# Adafruit_CharlieWing.net
KiCad netlist of a schematic drawn in EAGLE
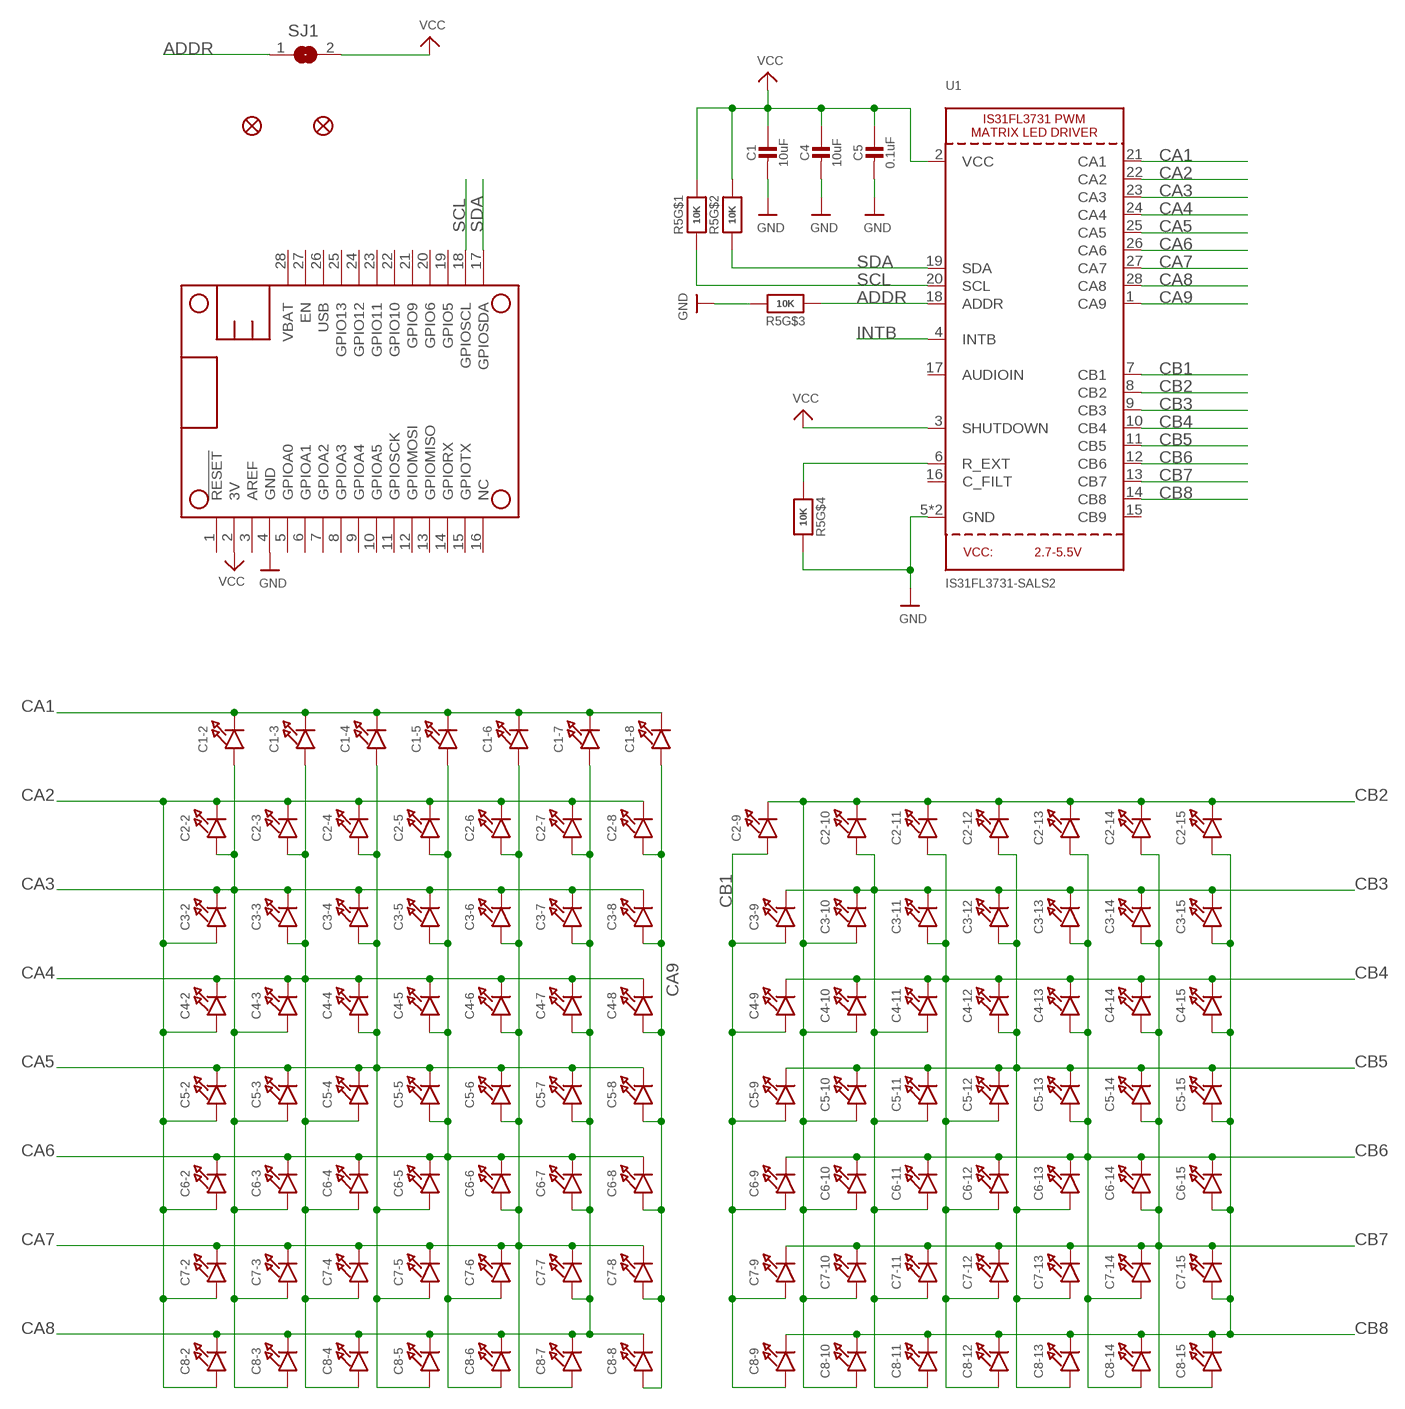
[diagram p0: schematic, sheet 1]

(export (version "E")
  (design (tool "Eeschema 10.0.6"))
  (components
    (comp (ref "C1")
      (value "10uF")
      (footprint "eagle-import:0805-NO")
      (libsource (lib "eagle-import") (part "CAP_CERAMIC0805-NOOUTLINE"))
    )
    (comp (ref "C1-2")
      (value "LED0603_NOOUTLINE")
      (footprint "eagle-import:CHIPLED_0603_NOOUTLINE")
      (libsource (lib "eagle-import") (part "LED0603_NOOUTLINE"))
    )
    (comp (ref "C1-3")
      (value "LED0603_NOOUTLINE")
      (footprint "eagle-import:CHIPLED_0603_NOOUTLINE")
      (libsource (lib "eagle-import") (part "LED0603_NOOUTLINE"))
    )
    (comp (ref "C1-4")
      (value "LED0603_NOOUTLINE")
      (footprint "eagle-import:CHIPLED_0603_NOOUTLINE")
      (libsource (lib "eagle-import") (part "LED0603_NOOUTLINE"))
    )
    (comp (ref "C1-5")
      (value "LED0603_NOOUTLINE")
      (footprint "eagle-import:CHIPLED_0603_NOOUTLINE")
      (libsource (lib "eagle-import") (part "LED0603_NOOUTLINE"))
    )
    (comp (ref "C1-6")
      (value "LED0603_NOOUTLINE")
      (footprint "eagle-import:CHIPLED_0603_NOOUTLINE")
      (libsource (lib "eagle-import") (part "LED0603_NOOUTLINE"))
    )
    (comp (ref "C1-7")
      (value "LED0603_NOOUTLINE")
      (footprint "eagle-import:CHIPLED_0603_NOOUTLINE")
      (libsource (lib "eagle-import") (part "LED0603_NOOUTLINE"))
    )
    (comp (ref "C1-8")
      (value "LED0603_NOOUTLINE")
      (footprint "eagle-import:CHIPLED_0603_NOOUTLINE")
      (libsource (lib "eagle-import") (part "LED0603_NOOUTLINE"))
    )
    (comp (ref "C2-2")
      (value "LED0603_NOOUTLINE")
      (footprint "eagle-import:CHIPLED_0603_NOOUTLINE")
      (libsource (lib "eagle-import") (part "LED0603_NOOUTLINE"))
    )
    (comp (ref "C2-3")
      (value "LED0603_NOOUTLINE")
      (footprint "eagle-import:CHIPLED_0603_NOOUTLINE")
      (libsource (lib "eagle-import") (part "LED0603_NOOUTLINE"))
    )
    (comp (ref "C2-4")
      (value "LED0603_NOOUTLINE")
      (footprint "eagle-import:CHIPLED_0603_NOOUTLINE")
      (libsource (lib "eagle-import") (part "LED0603_NOOUTLINE"))
    )
    (comp (ref "C2-5")
      (value "LED0603_NOOUTLINE")
      (footprint "eagle-import:CHIPLED_0603_NOOUTLINE")
      (libsource (lib "eagle-import") (part "LED0603_NOOUTLINE"))
    )
    (comp (ref "C2-6")
      (value "LED0603_NOOUTLINE")
      (footprint "eagle-import:CHIPLED_0603_NOOUTLINE")
      (libsource (lib "eagle-import") (part "LED0603_NOOUTLINE"))
    )
    (comp (ref "C2-7")
      (value "LED0603_NOOUTLINE")
      (footprint "eagle-import:CHIPLED_0603_NOOUTLINE")
      (libsource (lib "eagle-import") (part "LED0603_NOOUTLINE"))
    )
    (comp (ref "C2-8")
      (value "LED0603_NOOUTLINE")
      (footprint "eagle-import:CHIPLED_0603_NOOUTLINE")
      (libsource (lib "eagle-import") (part "LED0603_NOOUTLINE"))
    )
    (comp (ref "C2-9")
      (value "LED0603_NOOUTLINE")
      (footprint "eagle-import:CHIPLED_0603_NOOUTLINE")
      (libsource (lib "eagle-import") (part "LED0603_NOOUTLINE"))
    )
    (comp (ref "C2-10")
      (value "LED0603_NOOUTLINE")
      (footprint "eagle-import:CHIPLED_0603_NOOUTLINE")
      (libsource (lib "eagle-import") (part "LED0603_NOOUTLINE"))
    )
    (comp (ref "C2-11")
      (value "LED0603_NOOUTLINE")
      (footprint "eagle-import:CHIPLED_0603_NOOUTLINE")
      (libsource (lib "eagle-import") (part "LED0603_NOOUTLINE"))
    )
    (comp (ref "C2-12")
      (value "LED0603_NOOUTLINE")
      (footprint "eagle-import:CHIPLED_0603_NOOUTLINE")
      (libsource (lib "eagle-import") (part "LED0603_NOOUTLINE"))
    )
    (comp (ref "C2-13")
      (value "LED0603_NOOUTLINE")
      (footprint "eagle-import:CHIPLED_0603_NOOUTLINE")
      (libsource (lib "eagle-import") (part "LED0603_NOOUTLINE"))
    )
    (comp (ref "C2-14")
      (value "LED0603_NOOUTLINE")
      (footprint "eagle-import:CHIPLED_0603_NOOUTLINE")
      (libsource (lib "eagle-import") (part "LED0603_NOOUTLINE"))
    )
    (comp (ref "C2-15")
      (value "LED0603_NOOUTLINE")
      (footprint "eagle-import:CHIPLED_0603_NOOUTLINE")
      (libsource (lib "eagle-import") (part "LED0603_NOOUTLINE"))
    )
    (comp (ref "C3-2")
      (value "LED0603_NOOUTLINE")
      (footprint "eagle-import:CHIPLED_0603_NOOUTLINE")
      (libsource (lib "eagle-import") (part "LED0603_NOOUTLINE"))
    )
    (comp (ref "C3-3")
      (value "LED0603_NOOUTLINE")
      (footprint "eagle-import:CHIPLED_0603_NOOUTLINE")
      (libsource (lib "eagle-import") (part "LED0603_NOOUTLINE"))
    )
    (comp (ref "C3-4")
      (value "LED0603_NOOUTLINE")
      (footprint "eagle-import:CHIPLED_0603_NOOUTLINE")
      (libsource (lib "eagle-import") (part "LED0603_NOOUTLINE"))
    )
    (comp (ref "C3-5")
      (value "LED0603_NOOUTLINE")
      (footprint "eagle-import:CHIPLED_0603_NOOUTLINE")
      (libsource (lib "eagle-import") (part "LED0603_NOOUTLINE"))
    )
    (comp (ref "C3-6")
      (value "LED0603_NOOUTLINE")
      (footprint "eagle-import:CHIPLED_0603_NOOUTLINE")
      (libsource (lib "eagle-import") (part "LED0603_NOOUTLINE"))
    )
    (comp (ref "C3-7")
      (value "LED0603_NOOUTLINE")
      (footprint "eagle-import:CHIPLED_0603_NOOUTLINE")
      (libsource (lib "eagle-import") (part "LED0603_NOOUTLINE"))
    )
    (comp (ref "C3-8")
      (value "LED0603_NOOUTLINE")
      (footprint "eagle-import:CHIPLED_0603_NOOUTLINE")
      (libsource (lib "eagle-import") (part "LED0603_NOOUTLINE"))
    )
    (comp (ref "C3-9")
      (value "LED0603_NOOUTLINE")
      (footprint "eagle-import:CHIPLED_0603_NOOUTLINE")
      (libsource (lib "eagle-import") (part "LED0603_NOOUTLINE"))
    )
    (comp (ref "C3-10")
      (value "LED0603_NOOUTLINE")
      (footprint "eagle-import:CHIPLED_0603_NOOUTLINE")
      (libsource (lib "eagle-import") (part "LED0603_NOOUTLINE"))
    )
    (comp (ref "C3-11")
      (value "LED0603_NOOUTLINE")
      (footprint "eagle-import:CHIPLED_0603_NOOUTLINE")
      (libsource (lib "eagle-import") (part "LED0603_NOOUTLINE"))
    )
    (comp (ref "C3-12")
      (value "LED0603_NOOUTLINE")
      (footprint "eagle-import:CHIPLED_0603_NOOUTLINE")
      (libsource (lib "eagle-import") (part "LED0603_NOOUTLINE"))
    )
    (comp (ref "C3-13")
      (value "LED0603_NOOUTLINE")
      (footprint "eagle-import:CHIPLED_0603_NOOUTLINE")
      (libsource (lib "eagle-import") (part "LED0603_NOOUTLINE"))
    )
    (comp (ref "C3-14")
      (value "LED0603_NOOUTLINE")
      (footprint "eagle-import:CHIPLED_0603_NOOUTLINE")
      (libsource (lib "eagle-import") (part "LED0603_NOOUTLINE"))
    )
    (comp (ref "C3-15")
      (value "LED0603_NOOUTLINE")
      (footprint "eagle-import:CHIPLED_0603_NOOUTLINE")
      (libsource (lib "eagle-import") (part "LED0603_NOOUTLINE"))
    )
    (comp (ref "C4")
      (value "10uF")
      (footprint "eagle-import:0805-NO")
      (libsource (lib "eagle-import") (part "CAP_CERAMIC0805-NOOUTLINE"))
    )
    (comp (ref "C4-2")
      (value "LED0603_NOOUTLINE")
      (footprint "eagle-import:CHIPLED_0603_NOOUTLINE")
      (libsource (lib "eagle-import") (part "LED0603_NOOUTLINE"))
    )
    (comp (ref "C4-3")
      (value "LED0603_NOOUTLINE")
      (footprint "eagle-import:CHIPLED_0603_NOOUTLINE")
      (libsource (lib "eagle-import") (part "LED0603_NOOUTLINE"))
    )
    (comp (ref "C4-4")
      (value "LED0603_NOOUTLINE")
      (footprint "eagle-import:CHIPLED_0603_NOOUTLINE")
      (libsource (lib "eagle-import") (part "LED0603_NOOUTLINE"))
    )
    (comp (ref "C4-5")
      (value "LED0603_NOOUTLINE")
      (footprint "eagle-import:CHIPLED_0603_NOOUTLINE")
      (libsource (lib "eagle-import") (part "LED0603_NOOUTLINE"))
    )
    (comp (ref "C4-6")
      (value "LED0603_NOOUTLINE")
      (footprint "eagle-import:CHIPLED_0603_NOOUTLINE")
      (libsource (lib "eagle-import") (part "LED0603_NOOUTLINE"))
    )
    (comp (ref "C4-7")
      (value "LED0603_NOOUTLINE")
      (footprint "eagle-import:CHIPLED_0603_NOOUTLINE")
      (libsource (lib "eagle-import") (part "LED0603_NOOUTLINE"))
    )
    (comp (ref "C4-8")
      (value "LED0603_NOOUTLINE")
      (footprint "eagle-import:CHIPLED_0603_NOOUTLINE")
      (libsource (lib "eagle-import") (part "LED0603_NOOUTLINE"))
    )
    (comp (ref "C4-9")
      (value "LED0603_NOOUTLINE")
      (footprint "eagle-import:CHIPLED_0603_NOOUTLINE")
      (libsource (lib "eagle-import") (part "LED0603_NOOUTLINE"))
    )
    (comp (ref "C4-10")
      (value "LED0603_NOOUTLINE")
      (footprint "eagle-import:CHIPLED_0603_NOOUTLINE")
      (libsource (lib "eagle-import") (part "LED0603_NOOUTLINE"))
    )
    (comp (ref "C4-11")
      (value "LED0603_NOOUTLINE")
      (footprint "eagle-import:CHIPLED_0603_NOOUTLINE")
      (libsource (lib "eagle-import") (part "LED0603_NOOUTLINE"))
    )
    (comp (ref "C4-12")
      (value "LED0603_NOOUTLINE")
      (footprint "eagle-import:CHIPLED_0603_NOOUTLINE")
      (libsource (lib "eagle-import") (part "LED0603_NOOUTLINE"))
    )
    (comp (ref "C4-13")
      (value "LED0603_NOOUTLINE")
      (footprint "eagle-import:CHIPLED_0603_NOOUTLINE")
      (libsource (lib "eagle-import") (part "LED0603_NOOUTLINE"))
    )
    (comp (ref "C4-14")
      (value "LED0603_NOOUTLINE")
      (footprint "eagle-import:CHIPLED_0603_NOOUTLINE")
      (libsource (lib "eagle-import") (part "LED0603_NOOUTLINE"))
    )
    (comp (ref "C4-15")
      (value "LED0603_NOOUTLINE")
      (footprint "eagle-import:CHIPLED_0603_NOOUTLINE")
      (libsource (lib "eagle-import") (part "LED0603_NOOUTLINE"))
    )
    (comp (ref "C5")
      (value "0.1uF")
      (footprint "eagle-import:0805-NO")
      (libsource (lib "eagle-import") (part "CAP_CERAMIC0805-NOOUTLINE"))
    )
    (comp (ref "C5-2")
      (value "LED0603_NOOUTLINE")
      (footprint "eagle-import:CHIPLED_0603_NOOUTLINE")
      (libsource (lib "eagle-import") (part "LED0603_NOOUTLINE"))
    )
    (comp (ref "C5-3")
      (value "LED0603_NOOUTLINE")
      (footprint "eagle-import:CHIPLED_0603_NOOUTLINE")
      (libsource (lib "eagle-import") (part "LED0603_NOOUTLINE"))
    )
    (comp (ref "C5-4")
      (value "LED0603_NOOUTLINE")
      (footprint "eagle-import:CHIPLED_0603_NOOUTLINE")
      (libsource (lib "eagle-import") (part "LED0603_NOOUTLINE"))
    )
    (comp (ref "C5-5")
      (value "LED0603_NOOUTLINE")
      (footprint "eagle-import:CHIPLED_0603_NOOUTLINE")
      (libsource (lib "eagle-import") (part "LED0603_NOOUTLINE"))
    )
    (comp (ref "C5-6")
      (value "LED0603_NOOUTLINE")
      (footprint "eagle-import:CHIPLED_0603_NOOUTLINE")
      (libsource (lib "eagle-import") (part "LED0603_NOOUTLINE"))
    )
    (comp (ref "C5-7")
      (value "LED0603_NOOUTLINE")
      (footprint "eagle-import:CHIPLED_0603_NOOUTLINE")
      (libsource (lib "eagle-import") (part "LED0603_NOOUTLINE"))
    )
    (comp (ref "C5-8")
      (value "LED0603_NOOUTLINE")
      (footprint "eagle-import:CHIPLED_0603_NOOUTLINE")
      (libsource (lib "eagle-import") (part "LED0603_NOOUTLINE"))
    )
    (comp (ref "C5-9")
      (value "LED0603_NOOUTLINE")
      (footprint "eagle-import:CHIPLED_0603_NOOUTLINE")
      (libsource (lib "eagle-import") (part "LED0603_NOOUTLINE"))
    )
    (comp (ref "C5-10")
      (value "LED0603_NOOUTLINE")
      (footprint "eagle-import:CHIPLED_0603_NOOUTLINE")
      (libsource (lib "eagle-import") (part "LED0603_NOOUTLINE"))
    )
    (comp (ref "C5-11")
      (value "LED0603_NOOUTLINE")
      (footprint "eagle-import:CHIPLED_0603_NOOUTLINE")
      (libsource (lib "eagle-import") (part "LED0603_NOOUTLINE"))
    )
    (comp (ref "C5-12")
      (value "LED0603_NOOUTLINE")
      (footprint "eagle-import:CHIPLED_0603_NOOUTLINE")
      (libsource (lib "eagle-import") (part "LED0603_NOOUTLINE"))
    )
    (comp (ref "C5-13")
      (value "LED0603_NOOUTLINE")
      (footprint "eagle-import:CHIPLED_0603_NOOUTLINE")
      (libsource (lib "eagle-import") (part "LED0603_NOOUTLINE"))
    )
    (comp (ref "C5-14")
      (value "LED0603_NOOUTLINE")
      (footprint "eagle-import:CHIPLED_0603_NOOUTLINE")
      (libsource (lib "eagle-import") (part "LED0603_NOOUTLINE"))
    )
    (comp (ref "C5-15")
      (value "LED0603_NOOUTLINE")
      (footprint "eagle-import:CHIPLED_0603_NOOUTLINE")
      (libsource (lib "eagle-import") (part "LED0603_NOOUTLINE"))
    )
    (comp (ref "C6-2")
      (value "LED0603_NOOUTLINE")
      (footprint "eagle-import:CHIPLED_0603_NOOUTLINE")
      (libsource (lib "eagle-import") (part "LED0603_NOOUTLINE"))
    )
    (comp (ref "C6-3")
      (value "LED0603_NOOUTLINE")
      (footprint "eagle-import:CHIPLED_0603_NOOUTLINE")
      (libsource (lib "eagle-import") (part "LED0603_NOOUTLINE"))
    )
    (comp (ref "C6-4")
      (value "LED0603_NOOUTLINE")
      (footprint "eagle-import:CHIPLED_0603_NOOUTLINE")
      (libsource (lib "eagle-import") (part "LED0603_NOOUTLINE"))
    )
    (comp (ref "C6-5")
      (value "LED0603_NOOUTLINE")
      (footprint "eagle-import:CHIPLED_0603_NOOUTLINE")
      (libsource (lib "eagle-import") (part "LED0603_NOOUTLINE"))
    )
    (comp (ref "C6-6")
      (value "LED0603_NOOUTLINE")
      (footprint "eagle-import:CHIPLED_0603_NOOUTLINE")
      (libsource (lib "eagle-import") (part "LED0603_NOOUTLINE"))
    )
    (comp (ref "C6-7")
      (value "LED0603_NOOUTLINE")
      (footprint "eagle-import:CHIPLED_0603_NOOUTLINE")
      (libsource (lib "eagle-import") (part "LED0603_NOOUTLINE"))
    )
    (comp (ref "C6-8")
      (value "LED0603_NOOUTLINE")
      (footprint "eagle-import:CHIPLED_0603_NOOUTLINE")
      (libsource (lib "eagle-import") (part "LED0603_NOOUTLINE"))
    )
    (comp (ref "C6-9")
      (value "LED0603_NOOUTLINE")
      (footprint "eagle-import:CHIPLED_0603_NOOUTLINE")
      (libsource (lib "eagle-import") (part "LED0603_NOOUTLINE"))
    )
    (comp (ref "C6-10")
      (value "LED0603_NOOUTLINE")
      (footprint "eagle-import:CHIPLED_0603_NOOUTLINE")
      (libsource (lib "eagle-import") (part "LED0603_NOOUTLINE"))
    )
    (comp (ref "C6-11")
      (value "LED0603_NOOUTLINE")
      (footprint "eagle-import:CHIPLED_0603_NOOUTLINE")
      (libsource (lib "eagle-import") (part "LED0603_NOOUTLINE"))
    )
    (comp (ref "C6-12")
      (value "LED0603_NOOUTLINE")
      (footprint "eagle-import:CHIPLED_0603_NOOUTLINE")
      (libsource (lib "eagle-import") (part "LED0603_NOOUTLINE"))
    )
    (comp (ref "C6-13")
      (value "LED0603_NOOUTLINE")
      (footprint "eagle-import:CHIPLED_0603_NOOUTLINE")
      (libsource (lib "eagle-import") (part "LED0603_NOOUTLINE"))
    )
    (comp (ref "C6-14")
      (value "LED0603_NOOUTLINE")
      (footprint "eagle-import:CHIPLED_0603_NOOUTLINE")
      (libsource (lib "eagle-import") (part "LED0603_NOOUTLINE"))
    )
    (comp (ref "C6-15")
      (value "LED0603_NOOUTLINE")
      (footprint "eagle-import:CHIPLED_0603_NOOUTLINE")
      (libsource (lib "eagle-import") (part "LED0603_NOOUTLINE"))
    )
    (comp (ref "C7-2")
      (value "LED0603_NOOUTLINE")
      (footprint "eagle-import:CHIPLED_0603_NOOUTLINE")
      (libsource (lib "eagle-import") (part "LED0603_NOOUTLINE"))
    )
    (comp (ref "C7-3")
      (value "LED0603_NOOUTLINE")
      (footprint "eagle-import:CHIPLED_0603_NOOUTLINE")
      (libsource (lib "eagle-import") (part "LED0603_NOOUTLINE"))
    )
    (comp (ref "C7-4")
      (value "LED0603_NOOUTLINE")
      (footprint "eagle-import:CHIPLED_0603_NOOUTLINE")
      (libsource (lib "eagle-import") (part "LED0603_NOOUTLINE"))
    )
    (comp (ref "C7-5")
      (value "LED0603_NOOUTLINE")
      (footprint "eagle-import:CHIPLED_0603_NOOUTLINE")
      (libsource (lib "eagle-import") (part "LED0603_NOOUTLINE"))
    )
    (comp (ref "C7-6")
      (value "LED0603_NOOUTLINE")
      (footprint "eagle-import:CHIPLED_0603_NOOUTLINE")
      (libsource (lib "eagle-import") (part "LED0603_NOOUTLINE"))
    )
    (comp (ref "C7-7")
      (value "LED0603_NOOUTLINE")
      (footprint "eagle-import:CHIPLED_0603_NOOUTLINE")
      (libsource (lib "eagle-import") (part "LED0603_NOOUTLINE"))
    )
    (comp (ref "C7-8")
      (value "LED0603_NOOUTLINE")
      (footprint "eagle-import:CHIPLED_0603_NOOUTLINE")
      (libsource (lib "eagle-import") (part "LED0603_NOOUTLINE"))
    )
    (comp (ref "C7-9")
      (value "LED0603_NOOUTLINE")
      (footprint "eagle-import:CHIPLED_0603_NOOUTLINE")
      (libsource (lib "eagle-import") (part "LED0603_NOOUTLINE"))
    )
    (comp (ref "C7-10")
      (value "LED0603_NOOUTLINE")
      (footprint "eagle-import:CHIPLED_0603_NOOUTLINE")
      (libsource (lib "eagle-import") (part "LED0603_NOOUTLINE"))
    )
    (comp (ref "C7-11")
      (value "LED0603_NOOUTLINE")
      (footprint "eagle-import:CHIPLED_0603_NOOUTLINE")
      (libsource (lib "eagle-import") (part "LED0603_NOOUTLINE"))
    )
    (comp (ref "C7-12")
      (value "LED0603_NOOUTLINE")
      (footprint "eagle-import:CHIPLED_0603_NOOUTLINE")
      (libsource (lib "eagle-import") (part "LED0603_NOOUTLINE"))
    )
    (comp (ref "C7-13")
      (value "LED0603_NOOUTLINE")
      (footprint "eagle-import:CHIPLED_0603_NOOUTLINE")
      (libsource (lib "eagle-import") (part "LED0603_NOOUTLINE"))
    )
    (comp (ref "C7-14")
      (value "LED0603_NOOUTLINE")
      (footprint "eagle-import:CHIPLED_0603_NOOUTLINE")
      (libsource (lib "eagle-import") (part "LED0603_NOOUTLINE"))
    )
    (comp (ref "C7-15")
      (value "LED0603_NOOUTLINE")
      (footprint "eagle-import:CHIPLED_0603_NOOUTLINE")
      (libsource (lib "eagle-import") (part "LED0603_NOOUTLINE"))
    )
    (comp (ref "C8-2")
      (value "LED0603_NOOUTLINE")
      (footprint "eagle-import:CHIPLED_0603_NOOUTLINE")
      (libsource (lib "eagle-import") (part "LED0603_NOOUTLINE"))
    )
    (comp (ref "C8-3")
      (value "LED0603_NOOUTLINE")
      (footprint "eagle-import:CHIPLED_0603_NOOUTLINE")
      (libsource (lib "eagle-import") (part "LED0603_NOOUTLINE"))
    )
    (comp (ref "C8-4")
      (value "LED0603_NOOUTLINE")
      (footprint "eagle-import:CHIPLED_0603_NOOUTLINE")
      (libsource (lib "eagle-import") (part "LED0603_NOOUTLINE"))
    )
    (comp (ref "C8-5")
      (value "LED0603_NOOUTLINE")
      (footprint "eagle-import:CHIPLED_0603_NOOUTLINE")
      (libsource (lib "eagle-import") (part "LED0603_NOOUTLINE"))
    )
    (comp (ref "C8-6")
      (value "LED0603_NOOUTLINE")
      (footprint "eagle-import:CHIPLED_0603_NOOUTLINE")
      (libsource (lib "eagle-import") (part "LED0603_NOOUTLINE"))
    )
    (comp (ref "C8-7")
      (value "LED0603_NOOUTLINE")
      (footprint "eagle-import:CHIPLED_0603_NOOUTLINE")
      (libsource (lib "eagle-import") (part "LED0603_NOOUTLINE"))
    )
    (comp (ref "C8-8")
      (value "LED0603_NOOUTLINE")
      (footprint "eagle-import:CHIPLED_0603_NOOUTLINE")
      (libsource (lib "eagle-import") (part "LED0603_NOOUTLINE"))
    )
    (comp (ref "C8-9")
      (value "LED0603_NOOUTLINE")
      (footprint "eagle-import:CHIPLED_0603_NOOUTLINE")
      (libsource (lib "eagle-import") (part "LED0603_NOOUTLINE"))
    )
    (comp (ref "C8-10")
      (value "LED0603_NOOUTLINE")
      (footprint "eagle-import:CHIPLED_0603_NOOUTLINE")
      (libsource (lib "eagle-import") (part "LED0603_NOOUTLINE"))
    )
    (comp (ref "C8-11")
      (value "LED0603_NOOUTLINE")
      (footprint "eagle-import:CHIPLED_0603_NOOUTLINE")
      (libsource (lib "eagle-import") (part "LED0603_NOOUTLINE"))
    )
    (comp (ref "C8-12")
      (value "LED0603_NOOUTLINE")
      (footprint "eagle-import:CHIPLED_0603_NOOUTLINE")
      (libsource (lib "eagle-import") (part "LED0603_NOOUTLINE"))
    )
    (comp (ref "C8-13")
      (value "LED0603_NOOUTLINE")
      (footprint "eagle-import:CHIPLED_0603_NOOUTLINE")
      (libsource (lib "eagle-import") (part "LED0603_NOOUTLINE"))
    )
    (comp (ref "C8-14")
      (value "LED0603_NOOUTLINE")
      (footprint "eagle-import:CHIPLED_0603_NOOUTLINE")
      (libsource (lib "eagle-import") (part "LED0603_NOOUTLINE"))
    )
    (comp (ref "C8-15")
      (value "LED0603_NOOUTLINE")
      (footprint "eagle-import:CHIPLED_0603_NOOUTLINE")
      (libsource (lib "eagle-import") (part "LED0603_NOOUTLINE"))
    )
    (comp (ref "FID1")
      (value "FIDUCIAL\"\"")
      (footprint "eagle-import:FIDUCIAL_1MM")
      (libsource (lib "eagle-import") (part "FIDUCIAL{dblquote}{dblquote}"))
    )
    (comp (ref "FID2")
      (value "FIDUCIAL\"\"")
      (footprint "eagle-import:FIDUCIAL_1MM")
      (libsource (lib "eagle-import") (part "FIDUCIAL{dblquote}{dblquote}"))
    )
    (comp (ref "MS1")
      (value "FEATHERWING")
      (footprint "eagle-import:FEATHERWING")
      (libsource (lib "eagle-import") (part "FEATHERWING"))
    )
    (comp (ref "R5")
      (value "10K")
      (footprint "eagle-import:RESPACK_4X0603")
      (libsource (lib "eagle-import") (part "RESISTOR_4PACK"))
    )
    (comp (ref "SJ1")
      (value "SOLDERJUMPER")
      (footprint "eagle-import:SOLDERJUMPER_ARROW_NOPASTE")
      (libsource (lib "eagle-import") (part "SOLDERJUMPER"))
    )
    (comp (ref "U1")
      (value "IS31FL3731-SALS2")
      (footprint "eagle-import:QFN28_4MM_0.4MM")
      (libsource (lib "eagle-import") (part "IS31FL3731QFN"))
    )
  )
  (nets
    (net (code "1") (name "/ADDR") (class "Default")
      (node (ref "R5") (pin "3") (pinfunction "1_3") (pintype "passive"))
      (node (ref "SJ1") (pin "1") (pinfunction "1_1") (pintype "passive"))
      (node (ref "U1") (pin "18") (pinfunction "ADDR_18") (pintype "bidirectional"))
    )
    (net (code "2") (name "/CA1") (class "Default")
      (node (ref "C1-2") (pin "C") (pinfunction "C_C") (pintype "passive"))
      (node (ref "C1-3") (pin "C") (pinfunction "C_C") (pintype "passive"))
      (node (ref "C1-4") (pin "C") (pinfunction "C_C") (pintype "passive"))
      (node (ref "C1-5") (pin "C") (pinfunction "C_C") (pintype "passive"))
      (node (ref "C1-6") (pin "C") (pinfunction "C_C") (pintype "passive"))
      (node (ref "C1-7") (pin "C") (pinfunction "C_C") (pintype "passive"))
      (node (ref "C1-8") (pin "C") (pinfunction "C_C") (pintype "passive"))
      (node (ref "U1") (pin "21") (pinfunction "CA1_21") (pintype "bidirectional"))
    )
    (net (code "3") (name "/CA2") (class "Default")
      (node (ref "C2-2") (pin "C") (pinfunction "C_C") (pintype "passive"))
      (node (ref "C2-3") (pin "C") (pinfunction "C_C") (pintype "passive"))
      (node (ref "C2-4") (pin "C") (pinfunction "C_C") (pintype "passive"))
      (node (ref "C2-5") (pin "C") (pinfunction "C_C") (pintype "passive"))
      (node (ref "C2-6") (pin "C") (pinfunction "C_C") (pintype "passive"))
      (node (ref "C2-7") (pin "C") (pinfunction "C_C") (pintype "passive"))
      (node (ref "C2-8") (pin "C") (pinfunction "C_C") (pintype "passive"))
      (node (ref "C3-2") (pin "A") (pinfunction "A_A") (pintype "passive"))
      (node (ref "C4-2") (pin "A") (pinfunction "A_A") (pintype "passive"))
      (node (ref "C5-2") (pin "A") (pinfunction "A_A") (pintype "passive"))
      (node (ref "C6-2") (pin "A") (pinfunction "A_A") (pintype "passive"))
      (node (ref "C7-2") (pin "A") (pinfunction "A_A") (pintype "passive"))
      (node (ref "C8-2") (pin "A") (pinfunction "A_A") (pintype "passive"))
      (node (ref "U1") (pin "22") (pinfunction "CA2_22") (pintype "bidirectional"))
    )
    (net (code "4") (name "/CA3") (class "Default")
      (node (ref "C1-2") (pin "A") (pinfunction "A_A") (pintype "passive"))
      (node (ref "C2-2") (pin "A") (pinfunction "A_A") (pintype "passive"))
      (node (ref "C3-2") (pin "C") (pinfunction "C_C") (pintype "passive"))
      (node (ref "C3-3") (pin "C") (pinfunction "C_C") (pintype "passive"))
      (node (ref "C3-4") (pin "C") (pinfunction "C_C") (pintype "passive"))
      (node (ref "C3-5") (pin "C") (pinfunction "C_C") (pintype "passive"))
      (node (ref "C3-6") (pin "C") (pinfunction "C_C") (pintype "passive"))
      (node (ref "C3-7") (pin "C") (pinfunction "C_C") (pintype "passive"))
      (node (ref "C3-8") (pin "C") (pinfunction "C_C") (pintype "passive"))
      (node (ref "C4-3") (pin "A") (pinfunction "A_A") (pintype "passive"))
      (node (ref "C5-3") (pin "A") (pinfunction "A_A") (pintype "passive"))
      (node (ref "C6-3") (pin "A") (pinfunction "A_A") (pintype "passive"))
      (node (ref "C7-3") (pin "A") (pinfunction "A_A") (pintype "passive"))
      (node (ref "C8-3") (pin "A") (pinfunction "A_A") (pintype "passive"))
      (node (ref "U1") (pin "23") (pinfunction "CA3_23") (pintype "bidirectional"))
    )
    (net (code "5") (name "/CA4") (class "Default")
      (node (ref "C1-3") (pin "A") (pinfunction "A_A") (pintype "passive"))
      (node (ref "C2-3") (pin "A") (pinfunction "A_A") (pintype "passive"))
      (node (ref "C3-3") (pin "A") (pinfunction "A_A") (pintype "passive"))
      (node (ref "C4-2") (pin "C") (pinfunction "C_C") (pintype "passive"))
      (node (ref "C4-3") (pin "C") (pinfunction "C_C") (pintype "passive"))
      (node (ref "C4-4") (pin "C") (pinfunction "C_C") (pintype "passive"))
      (node (ref "C4-5") (pin "C") (pinfunction "C_C") (pintype "passive"))
      (node (ref "C4-6") (pin "C") (pinfunction "C_C") (pintype "passive"))
      (node (ref "C4-7") (pin "C") (pinfunction "C_C") (pintype "passive"))
      (node (ref "C4-8") (pin "C") (pinfunction "C_C") (pintype "passive"))
      (node (ref "C5-4") (pin "A") (pinfunction "A_A") (pintype "passive"))
      (node (ref "C6-4") (pin "A") (pinfunction "A_A") (pintype "passive"))
      (node (ref "C7-4") (pin "A") (pinfunction "A_A") (pintype "passive"))
      (node (ref "C8-4") (pin "A") (pinfunction "A_A") (pintype "passive"))
      (node (ref "U1") (pin "24") (pinfunction "CA4_24") (pintype "bidirectional"))
    )
    (net (code "6") (name "/CA5") (class "Default")
      (node (ref "C1-4") (pin "A") (pinfunction "A_A") (pintype "passive"))
      (node (ref "C2-4") (pin "A") (pinfunction "A_A") (pintype "passive"))
      (node (ref "C3-4") (pin "A") (pinfunction "A_A") (pintype "passive"))
      (node (ref "C4-4") (pin "A") (pinfunction "A_A") (pintype "passive"))
      (node (ref "C5-2") (pin "C") (pinfunction "C_C") (pintype "passive"))
      (node (ref "C5-3") (pin "C") (pinfunction "C_C") (pintype "passive"))
      (node (ref "C5-4") (pin "C") (pinfunction "C_C") (pintype "passive"))
      (node (ref "C5-5") (pin "C") (pinfunction "C_C") (pintype "passive"))
      (node (ref "C5-6") (pin "C") (pinfunction "C_C") (pintype "passive"))
      (node (ref "C5-7") (pin "C") (pinfunction "C_C") (pintype "passive"))
      (node (ref "C5-8") (pin "C") (pinfunction "C_C") (pintype "passive"))
      (node (ref "C6-5") (pin "A") (pinfunction "A_A") (pintype "passive"))
      (node (ref "C7-5") (pin "A") (pinfunction "A_A") (pintype "passive"))
      (node (ref "C8-5") (pin "A") (pinfunction "A_A") (pintype "passive"))
      (node (ref "U1") (pin "25") (pinfunction "CA5_25") (pintype "bidirectional"))
    )
    (net (code "7") (name "/CA6") (class "Default")
      (node (ref "C1-5") (pin "A") (pinfunction "A_A") (pintype "passive"))
      (node (ref "C2-5") (pin "A") (pinfunction "A_A") (pintype "passive"))
      (node (ref "C3-5") (pin "A") (pinfunction "A_A") (pintype "passive"))
      (node (ref "C4-5") (pin "A") (pinfunction "A_A") (pintype "passive"))
      (node (ref "C5-5") (pin "A") (pinfunction "A_A") (pintype "passive"))
      (node (ref "C6-2") (pin "C") (pinfunction "C_C") (pintype "passive"))
      (node (ref "C6-3") (pin "C") (pinfunction "C_C") (pintype "passive"))
      (node (ref "C6-4") (pin "C") (pinfunction "C_C") (pintype "passive"))
      (node (ref "C6-5") (pin "C") (pinfunction "C_C") (pintype "passive"))
      (node (ref "C6-6") (pin "C") (pinfunction "C_C") (pintype "passive"))
      (node (ref "C6-7") (pin "C") (pinfunction "C_C") (pintype "passive"))
      (node (ref "C6-8") (pin "C") (pinfunction "C_C") (pintype "passive"))
      (node (ref "C7-6") (pin "A") (pinfunction "A_A") (pintype "passive"))
      (node (ref "C8-6") (pin "A") (pinfunction "A_A") (pintype "passive"))
      (node (ref "U1") (pin "26") (pinfunction "CA6_26") (pintype "bidirectional"))
    )
    (net (code "8") (name "/CA7") (class "Default")
      (node (ref "C1-6") (pin "A") (pinfunction "A_A") (pintype "passive"))
      (node (ref "C2-6") (pin "A") (pinfunction "A_A") (pintype "passive"))
      (node (ref "C3-6") (pin "A") (pinfunction "A_A") (pintype "passive"))
      (node (ref "C4-6") (pin "A") (pinfunction "A_A") (pintype "passive"))
      (node (ref "C5-6") (pin "A") (pinfunction "A_A") (pintype "passive"))
      (node (ref "C6-6") (pin "A") (pinfunction "A_A") (pintype "passive"))
      (node (ref "C7-2") (pin "C") (pinfunction "C_C") (pintype "passive"))
      (node (ref "C7-3") (pin "C") (pinfunction "C_C") (pintype "passive"))
      (node (ref "C7-4") (pin "C") (pinfunction "C_C") (pintype "passive"))
      (node (ref "C7-5") (pin "C") (pinfunction "C_C") (pintype "passive"))
      (node (ref "C7-6") (pin "C") (pinfunction "C_C") (pintype "passive"))
      (node (ref "C7-7") (pin "C") (pinfunction "C_C") (pintype "passive"))
      (node (ref "C7-8") (pin "C") (pinfunction "C_C") (pintype "passive"))
      (node (ref "C8-7") (pin "A") (pinfunction "A_A") (pintype "passive"))
      (node (ref "U1") (pin "27") (pinfunction "CA7_27") (pintype "bidirectional"))
    )
    (net (code "9") (name "/CA8") (class "Default")
      (node (ref "C1-7") (pin "A") (pinfunction "A_A") (pintype "passive"))
      (node (ref "C2-7") (pin "A") (pinfunction "A_A") (pintype "passive"))
      (node (ref "C3-7") (pin "A") (pinfunction "A_A") (pintype "passive"))
      (node (ref "C4-7") (pin "A") (pinfunction "A_A") (pintype "passive"))
      (node (ref "C5-7") (pin "A") (pinfunction "A_A") (pintype "passive"))
      (node (ref "C6-7") (pin "A") (pinfunction "A_A") (pintype "passive"))
      (node (ref "C7-7") (pin "A") (pinfunction "A_A") (pintype "passive"))
      (node (ref "C8-2") (pin "C") (pinfunction "C_C") (pintype "passive"))
      (node (ref "C8-3") (pin "C") (pinfunction "C_C") (pintype "passive"))
      (node (ref "C8-4") (pin "C") (pinfunction "C_C") (pintype "passive"))
      (node (ref "C8-5") (pin "C") (pinfunction "C_C") (pintype "passive"))
      (node (ref "C8-6") (pin "C") (pinfunction "C_C") (pintype "passive"))
      (node (ref "C8-7") (pin "C") (pinfunction "C_C") (pintype "passive"))
      (node (ref "C8-8") (pin "C") (pinfunction "C_C") (pintype "passive"))
      (node (ref "U1") (pin "28") (pinfunction "CA8_28") (pintype "bidirectional"))
    )
    (net (code "10") (name "/CA9") (class "Default")
      (node (ref "C1-8") (pin "A") (pinfunction "A_A") (pintype "passive"))
      (node (ref "C2-8") (pin "A") (pinfunction "A_A") (pintype "passive"))
      (node (ref "C3-8") (pin "A") (pinfunction "A_A") (pintype "passive"))
      (node (ref "C4-8") (pin "A") (pinfunction "A_A") (pintype "passive"))
      (node (ref "C5-8") (pin "A") (pinfunction "A_A") (pintype "passive"))
      (node (ref "C6-8") (pin "A") (pinfunction "A_A") (pintype "passive"))
      (node (ref "C7-8") (pin "A") (pinfunction "A_A") (pintype "passive"))
      (node (ref "C8-8") (pin "A") (pinfunction "A_A") (pintype "passive"))
      (node (ref "U1") (pin "1") (pinfunction "CA9_1") (pintype "bidirectional"))
    )
    (net (code "11") (name "/CB1") (class "Default")
      (node (ref "C2-9") (pin "A") (pinfunction "A_A") (pintype "passive"))
      (node (ref "C3-9") (pin "A") (pinfunction "A_A") (pintype "passive"))
      (node (ref "C4-9") (pin "A") (pinfunction "A_A") (pintype "passive"))
      (node (ref "C5-9") (pin "A") (pinfunction "A_A") (pintype "passive"))
      (node (ref "C6-9") (pin "A") (pinfunction "A_A") (pintype "passive"))
      (node (ref "C7-9") (pin "A") (pinfunction "A_A") (pintype "passive"))
      (node (ref "C8-9") (pin "A") (pinfunction "A_A") (pintype "passive"))
      (node (ref "U1") (pin "7") (pinfunction "CB1_7") (pintype "bidirectional"))
    )
    (net (code "12") (name "/CB2") (class "Default")
      (node (ref "C2-10") (pin "C") (pinfunction "C_C") (pintype "passive"))
      (node (ref "C2-11") (pin "C") (pinfunction "C_C") (pintype "passive"))
      (node (ref "C2-12") (pin "C") (pinfunction "C_C") (pintype "passive"))
      (node (ref "C2-13") (pin "C") (pinfunction "C_C") (pintype "passive"))
      (node (ref "C2-14") (pin "C") (pinfunction "C_C") (pintype "passive"))
      (node (ref "C2-15") (pin "C") (pinfunction "C_C") (pintype "passive"))
      (node (ref "C2-9") (pin "C") (pinfunction "C_C") (pintype "passive"))
      (node (ref "C3-10") (pin "A") (pinfunction "A_A") (pintype "passive"))
      (node (ref "C4-10") (pin "A") (pinfunction "A_A") (pintype "passive"))
      (node (ref "C5-10") (pin "A") (pinfunction "A_A") (pintype "passive"))
      (node (ref "C6-10") (pin "A") (pinfunction "A_A") (pintype "passive"))
      (node (ref "C7-10") (pin "A") (pinfunction "A_A") (pintype "passive"))
      (node (ref "C8-10") (pin "A") (pinfunction "A_A") (pintype "passive"))
      (node (ref "U1") (pin "8") (pinfunction "CB2_8") (pintype "bidirectional"))
    )
    (net (code "13") (name "/CB3") (class "Default")
      (node (ref "C2-10") (pin "A") (pinfunction "A_A") (pintype "passive"))
      (node (ref "C3-10") (pin "C") (pinfunction "C_C") (pintype "passive"))
      (node (ref "C3-11") (pin "C") (pinfunction "C_C") (pintype "passive"))
      (node (ref "C3-12") (pin "C") (pinfunction "C_C") (pintype "passive"))
      (node (ref "C3-13") (pin "C") (pinfunction "C_C") (pintype "passive"))
      (node (ref "C3-14") (pin "C") (pinfunction "C_C") (pintype "passive"))
      (node (ref "C3-15") (pin "C") (pinfunction "C_C") (pintype "passive"))
      (node (ref "C3-9") (pin "C") (pinfunction "C_C") (pintype "passive"))
      (node (ref "C4-11") (pin "A") (pinfunction "A_A") (pintype "passive"))
      (node (ref "C5-11") (pin "A") (pinfunction "A_A") (pintype "passive"))
      (node (ref "C6-11") (pin "A") (pinfunction "A_A") (pintype "passive"))
      (node (ref "C7-11") (pin "A") (pinfunction "A_A") (pintype "passive"))
      (node (ref "C8-11") (pin "A") (pinfunction "A_A") (pintype "passive"))
      (node (ref "U1") (pin "9") (pinfunction "CB3_9") (pintype "bidirectional"))
    )
    (net (code "14") (name "/CB4") (class "Default")
      (node (ref "C2-11") (pin "A") (pinfunction "A_A") (pintype "passive"))
      (node (ref "C3-11") (pin "A") (pinfunction "A_A") (pintype "passive"))
      (node (ref "C4-10") (pin "C") (pinfunction "C_C") (pintype "passive"))
      (node (ref "C4-11") (pin "C") (pinfunction "C_C") (pintype "passive"))
      (node (ref "C4-12") (pin "C") (pinfunction "C_C") (pintype "passive"))
      (node (ref "C4-13") (pin "C") (pinfunction "C_C") (pintype "passive"))
      (node (ref "C4-14") (pin "C") (pinfunction "C_C") (pintype "passive"))
      (node (ref "C4-15") (pin "C") (pinfunction "C_C") (pintype "passive"))
      (node (ref "C4-9") (pin "C") (pinfunction "C_C") (pintype "passive"))
      (node (ref "C5-12") (pin "A") (pinfunction "A_A") (pintype "passive"))
      (node (ref "C6-12") (pin "A") (pinfunction "A_A") (pintype "passive"))
      (node (ref "C7-12") (pin "A") (pinfunction "A_A") (pintype "passive"))
      (node (ref "C8-12") (pin "A") (pinfunction "A_A") (pintype "passive"))
      (node (ref "U1") (pin "10") (pinfunction "CB4_10") (pintype "bidirectional"))
    )
    (net (code "15") (name "/CB5") (class "Default")
      (node (ref "C2-12") (pin "A") (pinfunction "A_A") (pintype "passive"))
      (node (ref "C3-12") (pin "A") (pinfunction "A_A") (pintype "passive"))
      (node (ref "C4-12") (pin "A") (pinfunction "A_A") (pintype "passive"))
      (node (ref "C5-10") (pin "C") (pinfunction "C_C") (pintype "passive"))
      (node (ref "C5-11") (pin "C") (pinfunction "C_C") (pintype "passive"))
      (node (ref "C5-12") (pin "C") (pinfunction "C_C") (pintype "passive"))
      (node (ref "C5-13") (pin "C") (pinfunction "C_C") (pintype "passive"))
      (node (ref "C5-14") (pin "C") (pinfunction "C_C") (pintype "passive"))
      (node (ref "C5-15") (pin "C") (pinfunction "C_C") (pintype "passive"))
      (node (ref "C5-9") (pin "C") (pinfunction "C_C") (pintype "passive"))
      (node (ref "C6-13") (pin "A") (pinfunction "A_A") (pintype "passive"))
      (node (ref "C7-13") (pin "A") (pinfunction "A_A") (pintype "passive"))
      (node (ref "C8-13") (pin "A") (pinfunction "A_A") (pintype "passive"))
      (node (ref "U1") (pin "11") (pinfunction "CB5_11") (pintype "bidirectional"))
    )
    (net (code "16") (name "/CB6") (class "Default")
      (node (ref "C2-13") (pin "A") (pinfunction "A_A") (pintype "passive"))
      (node (ref "C3-13") (pin "A") (pinfunction "A_A") (pintype "passive"))
      (node (ref "C4-13") (pin "A") (pinfunction "A_A") (pintype "passive"))
      (node (ref "C5-13") (pin "A") (pinfunction "A_A") (pintype "passive"))
      (node (ref "C6-10") (pin "C") (pinfunction "C_C") (pintype "passive"))
      (node (ref "C6-11") (pin "C") (pinfunction "C_C") (pintype "passive"))
      (node (ref "C6-12") (pin "C") (pinfunction "C_C") (pintype "passive"))
      (node (ref "C6-13") (pin "C") (pinfunction "C_C") (pintype "passive"))
      (node (ref "C6-14") (pin "C") (pinfunction "C_C") (pintype "passive"))
      (node (ref "C6-15") (pin "C") (pinfunction "C_C") (pintype "passive"))
      (node (ref "C6-9") (pin "C") (pinfunction "C_C") (pintype "passive"))
      (node (ref "C7-14") (pin "A") (pinfunction "A_A") (pintype "passive"))
      (node (ref "C8-14") (pin "A") (pinfunction "A_A") (pintype "passive"))
      (node (ref "U1") (pin "12") (pinfunction "CB6_12") (pintype "bidirectional"))
    )
    (net (code "17") (name "/CB7") (class "Default")
      (node (ref "C2-14") (pin "A") (pinfunction "A_A") (pintype "passive"))
      (node (ref "C3-14") (pin "A") (pinfunction "A_A") (pintype "passive"))
      (node (ref "C4-14") (pin "A") (pinfunction "A_A") (pintype "passive"))
      (node (ref "C5-14") (pin "A") (pinfunction "A_A") (pintype "passive"))
      (node (ref "C6-14") (pin "A") (pinfunction "A_A") (pintype "passive"))
      (node (ref "C7-10") (pin "C") (pinfunction "C_C") (pintype "passive"))
      (node (ref "C7-11") (pin "C") (pinfunction "C_C") (pintype "passive"))
      (node (ref "C7-12") (pin "C") (pinfunction "C_C") (pintype "passive"))
      (node (ref "C7-13") (pin "C") (pinfunction "C_C") (pintype "passive"))
      (node (ref "C7-14") (pin "C") (pinfunction "C_C") (pintype "passive"))
      (node (ref "C7-15") (pin "C") (pinfunction "C_C") (pintype "passive"))
      (node (ref "C7-9") (pin "C") (pinfunction "C_C") (pintype "passive"))
      (node (ref "C8-15") (pin "A") (pinfunction "A_A") (pintype "passive"))
      (node (ref "U1") (pin "13") (pinfunction "CB7_13") (pintype "bidirectional"))
    )
    (net (code "18") (name "/CB8") (class "Default")
      (node (ref "C2-15") (pin "A") (pinfunction "A_A") (pintype "passive"))
      (node (ref "C3-15") (pin "A") (pinfunction "A_A") (pintype "passive"))
      (node (ref "C4-15") (pin "A") (pinfunction "A_A") (pintype "passive"))
      (node (ref "C5-15") (pin "A") (pinfunction "A_A") (pintype "passive"))
      (node (ref "C6-15") (pin "A") (pinfunction "A_A") (pintype "passive"))
      (node (ref "C7-15") (pin "A") (pinfunction "A_A") (pintype "passive"))
      (node (ref "C8-10") (pin "C") (pinfunction "C_C") (pintype "passive"))
      (node (ref "C8-11") (pin "C") (pinfunction "C_C") (pintype "passive"))
      (node (ref "C8-12") (pin "C") (pinfunction "C_C") (pintype "passive"))
      (node (ref "C8-13") (pin "C") (pinfunction "C_C") (pintype "passive"))
      (node (ref "C8-14") (pin "C") (pinfunction "C_C") (pintype "passive"))
      (node (ref "C8-15") (pin "C") (pinfunction "C_C") (pintype "passive"))
      (node (ref "C8-9") (pin "C") (pinfunction "C_C") (pintype "passive"))
      (node (ref "U1") (pin "14") (pinfunction "CB8_14") (pintype "bidirectional"))
    )
    (net (code "19") (name "/INTB") (class "Default")
      (node (ref "U1") (pin "4") (pinfunction "INTB_4") (pintype "output"))
    )
    (net (code "20") (name "/SCL") (class "Default")
      (node (ref "MS1") (pin "18") (pinfunction "GPIOSCL_18") (pintype "bidirectional"))
      (node (ref "R5") (pin "1") (pinfunction "1_1") (pintype "passive"))
      (node (ref "U1") (pin "20") (pinfunction "SCL_20") (pintype "bidirectional"))
    )
    (net (code "21") (name "/SDA") (class "Default")
      (node (ref "MS1") (pin "17") (pinfunction "GPIOSDA_17") (pintype "bidirectional"))
      (node (ref "R5") (pin "2") (pinfunction "1_2") (pintype "passive"))
      (node (ref "U1") (pin "19") (pinfunction "SDA_19") (pintype "bidirectional"))
    )
    (net (code "22") (name "/USB") (class "Default")
      (node (ref "MS1") (pin "26") (pinfunction "USB_26") (pintype "power_in"))
    )
    (net (code "23") (name "/VBAT") (class "Default")
      (node (ref "MS1") (pin "28") (pinfunction "VBAT_28") (pintype "power_in"))
    )
    (net (code "24") (name "GND") (class "Default")
      (node (ref "C1") (pin "2") (pinfunction "2_2") (pintype "passive"))
      (node (ref "C4") (pin "2") (pinfunction "2_2") (pintype "passive"))
      (node (ref "C5") (pin "2") (pinfunction "2_2") (pintype "passive"))
      (node (ref "MS1") (pin "4") (pinfunction "GND_4") (pintype "power_in"))
      (node (ref "R5") (pin "5") (pinfunction "2_5") (pintype "passive"))
      (node (ref "R5") (pin "6") (pinfunction "2_6") (pintype "passive"))
      (node (ref "U1") (pin "5") (pinfunction "GND_5") (pintype "power_in"))
      (node (ref "U1") (pin "THERMAL") (pinfunction "GND_THERMAL") (pintype "power_in"))
    )
    (net (code "25") (name "Net-(R5D-1)") (class "Default")
      (node (ref "R5") (pin "4") (pinfunction "1_4") (pintype "passive"))
      (node (ref "U1") (pin "6") (pinfunction "R_EXT_6") (pintype "bidirectional"))
    )
    (net (code "26") (name "VCC") (class "Default")
      (node (ref "C1") (pin "1") (pinfunction "1_1") (pintype "passive"))
      (node (ref "C4") (pin "1") (pinfunction "1_1") (pintype "passive"))
      (node (ref "C5") (pin "1") (pinfunction "1_1") (pintype "passive"))
      (node (ref "MS1") (pin "2") (pinfunction "3V_2") (pintype "power_in"))
      (node (ref "R5") (pin "7") (pinfunction "2_7") (pintype "passive"))
      (node (ref "R5") (pin "8") (pinfunction "2_8") (pintype "passive"))
      (node (ref "SJ1") (pin "2") (pinfunction "2_2") (pintype "passive"))
      (node (ref "U1") (pin "2") (pinfunction "VCC_2") (pintype "power_in"))
      (node (ref "U1") (pin "3") (pinfunction "SHUTDOWN_3") (pintype "input"))
    )
    (net (code "27") (name "unconnected-(MS1-AREF-Pad3)") (class "Default")
      (node (ref "MS1") (pin "3") (pinfunction "AREF_3") (pintype "passive"))
    )
    (net (code "28") (name "unconnected-(MS1-EN-Pad27)") (class "Default")
      (node (ref "MS1") (pin "27") (pinfunction "EN_27") (pintype "passive"))
    )
    (net (code "29") (name "unconnected-(MS1-GPIO5-Pad19)") (class "Default")
      (node (ref "MS1") (pin "19") (pinfunction "GPIO5_19") (pintype "bidirectional"))
    )
    (net (code "30") (name "unconnected-(MS1-GPIO6-Pad20)") (class "Default")
      (node (ref "MS1") (pin "20") (pinfunction "GPIO6_20") (pintype "bidirectional"))
    )
    (net (code "31") (name "unconnected-(MS1-GPIO9-Pad21)") (class "Default")
      (node (ref "MS1") (pin "21") (pinfunction "GPIO9_21") (pintype "bidirectional"))
    )
    (net (code "32") (name "unconnected-(MS1-GPIO10-Pad22)") (class "Default")
      (node (ref "MS1") (pin "22") (pinfunction "GPIO10_22") (pintype "bidirectional"))
    )
    (net (code "33") (name "unconnected-(MS1-GPIO11-Pad23)") (class "Default")
      (node (ref "MS1") (pin "23") (pinfunction "GPIO11_23") (pintype "bidirectional"))
    )
    (net (code "34") (name "unconnected-(MS1-GPIO12-Pad24)") (class "Default")
      (node (ref "MS1") (pin "24") (pinfunction "GPIO12_24") (pintype "bidirectional"))
    )
    (net (code "35") (name "unconnected-(MS1-GPIO13-Pad25)") (class "Default")
      (node (ref "MS1") (pin "25") (pinfunction "GPIO13_25") (pintype "bidirectional"))
    )
    (net (code "36") (name "unconnected-(MS1-GPIOA0-Pad5)") (class "Default")
      (node (ref "MS1") (pin "5") (pinfunction "GPIOA0_5") (pintype "bidirectional"))
    )
    (net (code "37") (name "unconnected-(MS1-GPIOA1-Pad6)") (class "Default")
      (node (ref "MS1") (pin "6") (pinfunction "GPIOA1_6") (pintype "bidirectional"))
    )
    (net (code "38") (name "unconnected-(MS1-GPIOA2-Pad7)") (class "Default")
      (node (ref "MS1") (pin "7") (pinfunction "GPIOA2_7") (pintype "bidirectional"))
    )
    (net (code "39") (name "unconnected-(MS1-GPIOA3-Pad8)") (class "Default")
      (node (ref "MS1") (pin "8") (pinfunction "GPIOA3_8") (pintype "bidirectional"))
    )
    (net (code "40") (name "unconnected-(MS1-GPIOA4-Pad9)") (class "Default")
      (node (ref "MS1") (pin "9") (pinfunction "GPIOA4_9") (pintype "bidirectional"))
    )
    (net (code "41") (name "unconnected-(MS1-GPIOA5-Pad10)") (class "Default")
      (node (ref "MS1") (pin "10") (pinfunction "GPIOA5_10") (pintype "bidirectional"))
    )
    (net (code "42") (name "unconnected-(MS1-GPIOMISO-Pad13)") (class "Default")
      (node (ref "MS1") (pin "13") (pinfunction "GPIOMISO_13") (pintype "bidirectional"))
    )
    (net (code "43") (name "unconnected-(MS1-GPIOMOSI-Pad12)") (class "Default")
      (node (ref "MS1") (pin "12") (pinfunction "GPIOMOSI_12") (pintype "bidirectional"))
    )
    (net (code "44") (name "unconnected-(MS1-GPIORX-Pad14)") (class "Default")
      (node (ref "MS1") (pin "14") (pinfunction "GPIORX_14") (pintype "bidirectional"))
    )
    (net (code "45") (name "unconnected-(MS1-GPIOSCK-Pad11)") (class "Default")
      (node (ref "MS1") (pin "11") (pinfunction "GPIOSCK_11") (pintype "bidirectional"))
    )
    (net (code "46") (name "unconnected-(MS1-GPIOTX-Pad15)") (class "Default")
      (node (ref "MS1") (pin "15") (pinfunction "GPIOTX_15") (pintype "bidirectional"))
    )
    (net (code "47") (name "unconnected-(MS1-NC-Pad16)") (class "Default")
      (node (ref "MS1") (pin "16") (pinfunction "NC_16") (pintype "passive"))
    )
    (net (code "48") (name "unconnected-(MS1-~{RESET}-Pad1)") (class "Default")
      (node (ref "MS1") (pin "1") (pinfunction "~{RESET}_1") (pintype "input"))
    )
    (net (code "49") (name "unconnected-(U1-AUDIOIN-Pad17)") (class "Default")
      (node (ref "U1") (pin "17") (pinfunction "AUDIOIN_17") (pintype "input"))
    )
    (net (code "50") (name "unconnected-(U1-CB9-Pad15)") (class "Default")
      (node (ref "U1") (pin "15") (pinfunction "CB9_15") (pintype "bidirectional"))
    )
    (net (code "51") (name "unconnected-(U1-C_FILT-Pad16)") (class "Default")
      (node (ref "U1") (pin "16") (pinfunction "C_FILT_16") (pintype "bidirectional"))
    )
  )
)
